# 02_INPUT_PWR_2.net
KiCad netlist of a schematic drawn in Altium Designer
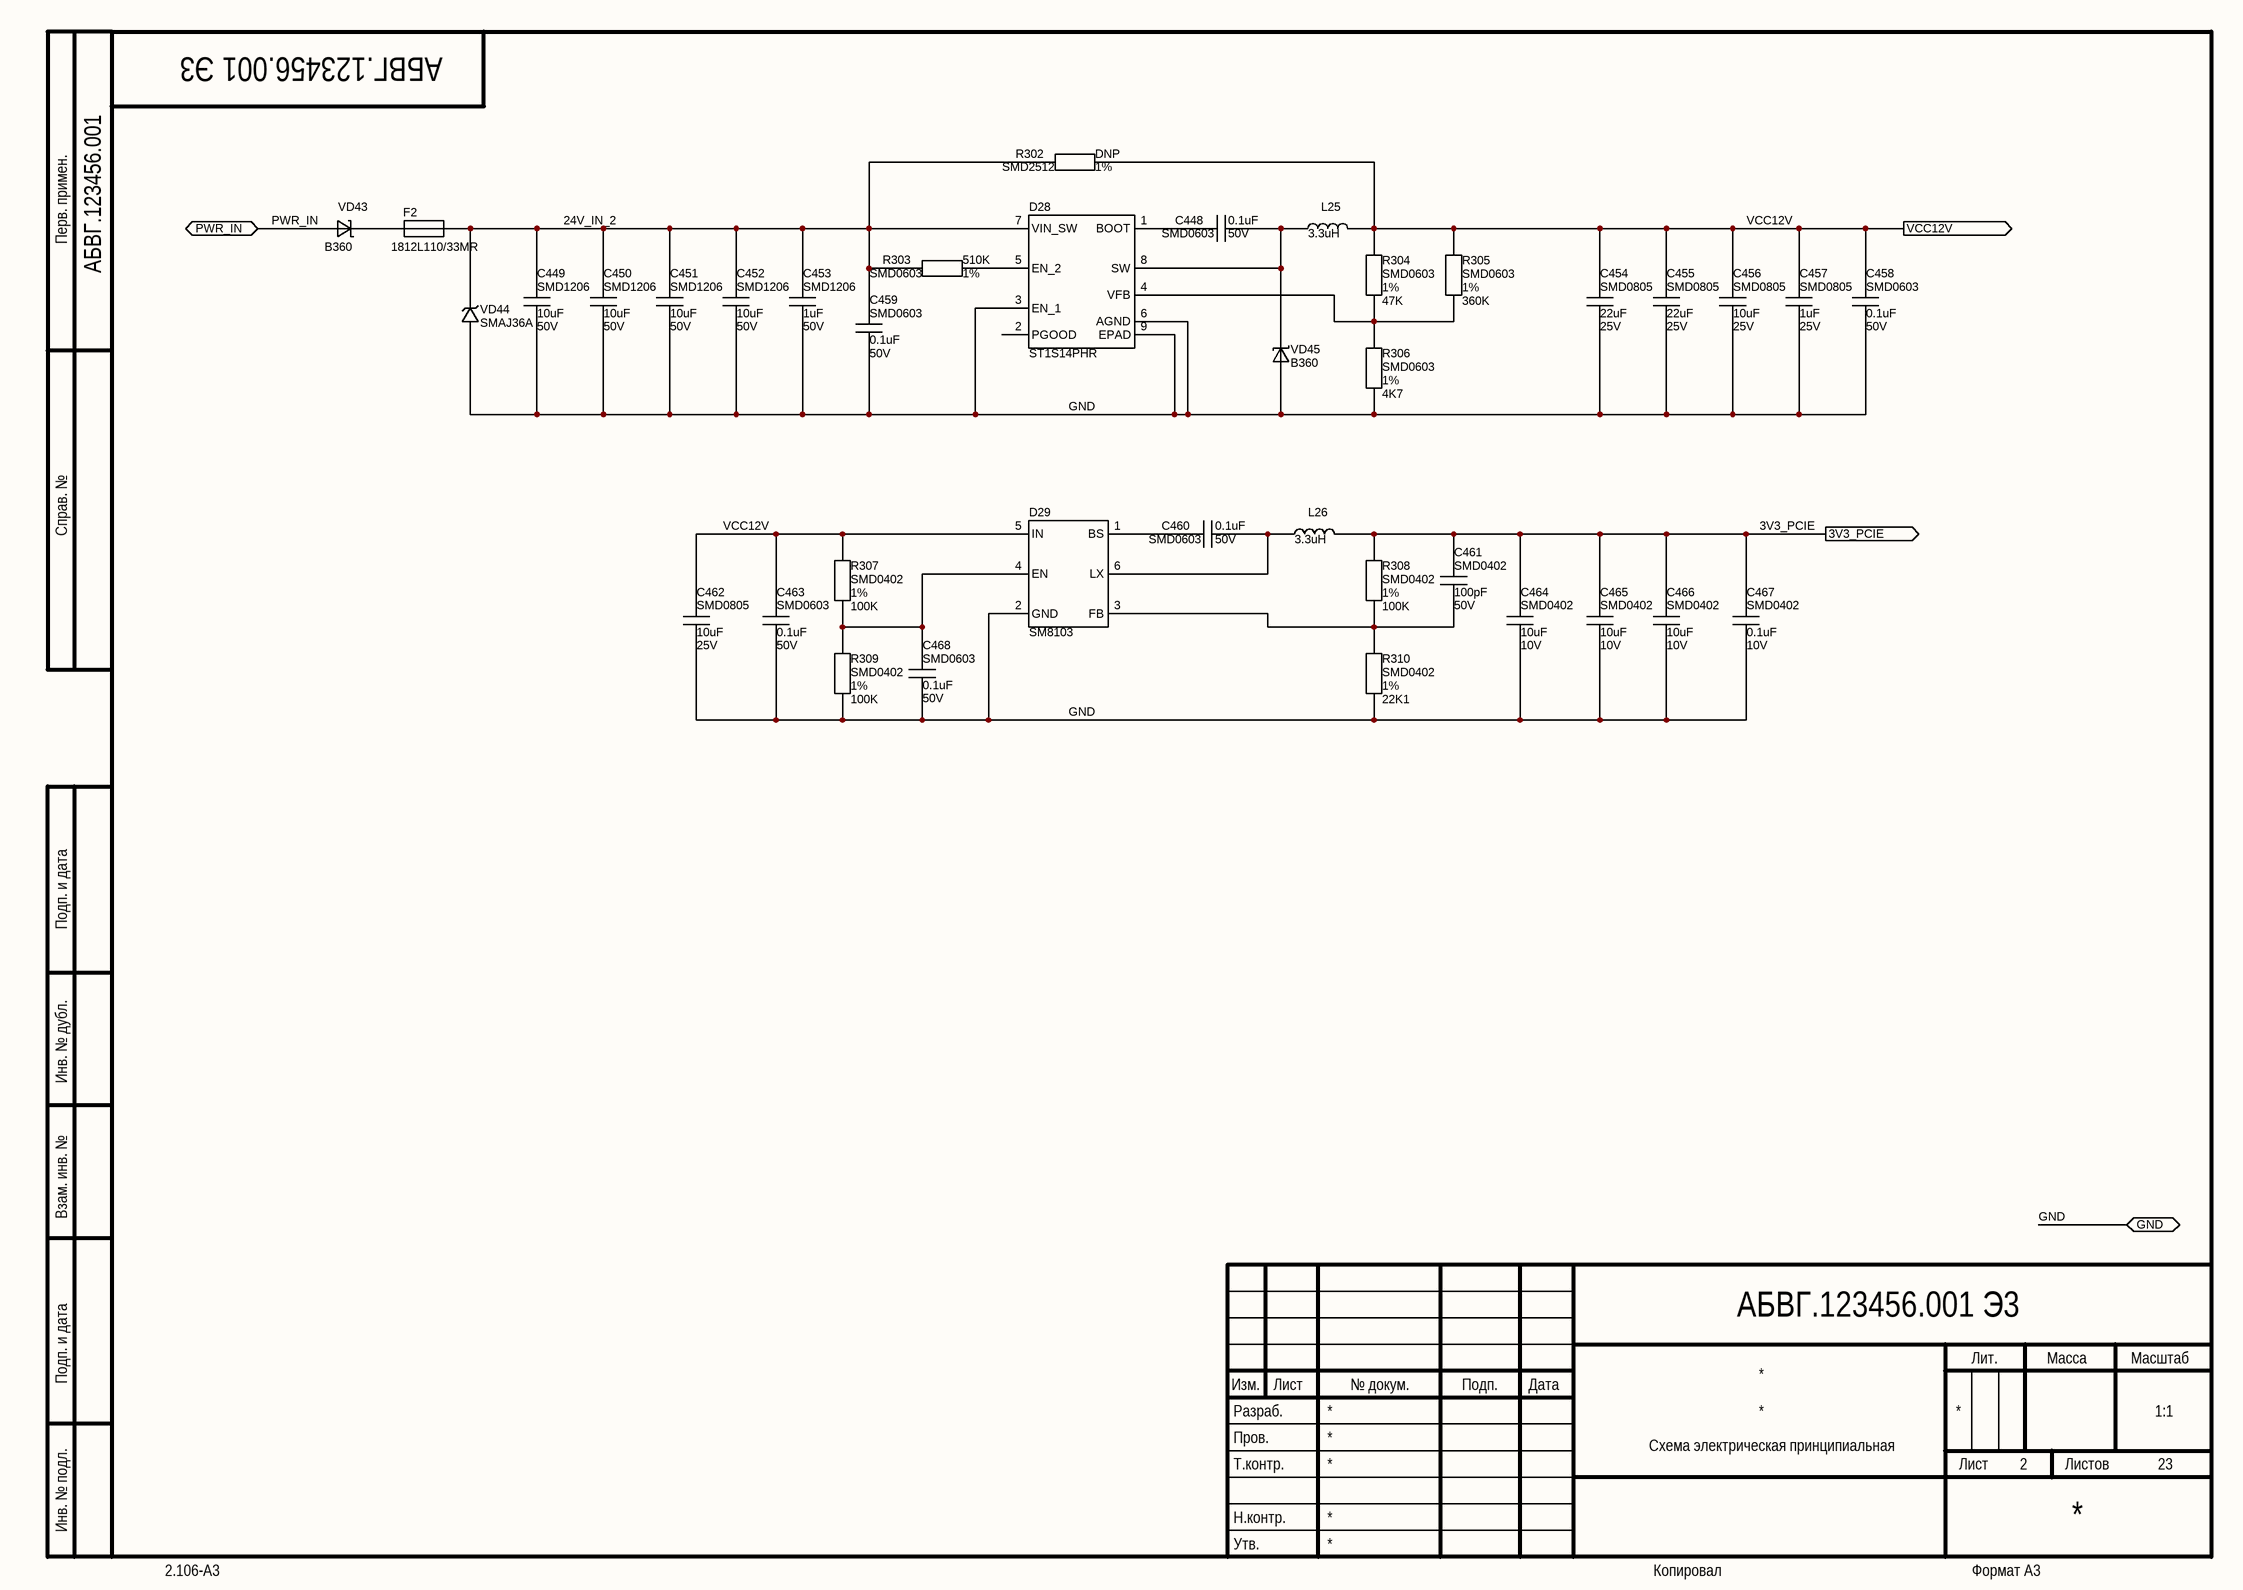
[diagram p0: 02 INPUT_PWR_2.SchDoc]

(export (version "E")
  (design (tool "Eeschema 10.0.6"))
  (components
    (comp (ref "C448")
      (value "0.1uF")
      (footprint "CAP_SMD_0603")
      (fields
        (field (name "PACKAGE") "SMD0603")
        (field (name "PARTNUMBER") "CC0603KRX7R9BB104")
        (field (name "VOLTAGE") "50V")
      )
      (libsource (lib "Didur_SchLib_1") (part "Ceramic_Cap"))
    )
    (comp (ref "C449")
      (value "10uF")
      (footprint "CAP_SMD_1206")
      (fields
        (field (name "PACKAGE") "SMD1206")
        (field (name "PARTNUMBER") "CL31B106KBHNNNE")
        (field (name "VOLTAGE") "50V")
      )
      (libsource (lib "Didur_SchLib_1") (part "Ceramic_Cap"))
    )
    (comp (ref "C450")
      (value "10uF")
      (footprint "CAP_SMD_1206")
      (fields
        (field (name "PACKAGE") "SMD1206")
        (field (name "PARTNUMBER") "CL31B106KBHNNNE")
        (field (name "VOLTAGE") "50V")
      )
      (libsource (lib "Didur_SchLib_1") (part "Ceramic_Cap"))
    )
    (comp (ref "C451")
      (value "10uF")
      (footprint "CAP_SMD_1206")
      (fields
        (field (name "PACKAGE") "SMD1206")
        (field (name "PARTNUMBER") "CL31B106KBHNNNE")
        (field (name "VOLTAGE") "50V")
      )
      (libsource (lib "Didur_SchLib_1") (part "Ceramic_Cap"))
    )
    (comp (ref "C452")
      (value "10uF")
      (footprint "CAP_SMD_1206")
      (fields
        (field (name "PACKAGE") "SMD1206")
        (field (name "PARTNUMBER") "CL31B106KBHNNNE")
        (field (name "VOLTAGE") "50V")
      )
      (libsource (lib "Didur_SchLib_1") (part "Ceramic_Cap"))
    )
    (comp (ref "C453")
      (value "1uF")
      (footprint "CAP_SMD_1206")
      (fields
        (field (name "PACKAGE") "SMD1206")
        (field (name "PARTNUMBER") "CC1206MRY5V9BB105")
        (field (name "VOLTAGE") "50V")
      )
      (libsource (lib "Didur_SchLib_1") (part "Ceramic_Cap"))
    )
    (comp (ref "C454")
      (value "22uF")
      (footprint "CAP_SMD_0805")
      (fields
        (field (name "PACKAGE") "SMD0805")
        (field (name "PARTNUMBER") "CC0805MKX5R8BB226")
        (field (name "VOLTAGE") "25V")
      )
      (libsource (lib "Didur_SchLib_1") (part "Ceramic_Cap"))
    )
    (comp (ref "C455")
      (value "22uF")
      (footprint "CAP_SMD_0805")
      (fields
        (field (name "PACKAGE") "SMD0805")
        (field (name "PARTNUMBER") "CC0805MKX5R8BB226")
        (field (name "VOLTAGE") "25V")
      )
      (libsource (lib "Didur_SchLib_1") (part "Ceramic_Cap"))
    )
    (comp (ref "C456")
      (value "10uF")
      (footprint "CAP_SMD_0805")
      (fields
        (field (name "PACKAGE") "SMD0805")
        (field (name "PARTNUMBER") "CL21A106KAYNNNE")
        (field (name "VOLTAGE") "25V")
      )
      (libsource (lib "Didur_SchLib_1") (part "Ceramic_Cap"))
    )
    (comp (ref "C457")
      (value "1uF")
      (footprint "CAP_SMD_0805")
      (fields
        (field (name "PACKAGE") "SMD0805")
        (field (name "PARTNUMBER") "CC0805KKX7R8BB105")
        (field (name "VOLTAGE") "25V")
      )
      (libsource (lib "Didur_SchLib_1") (part "Ceramic_Cap"))
    )
    (comp (ref "C458")
      (value "0.1uF")
      (footprint "CAP_SMD_0603")
      (fields
        (field (name "PACKAGE") "SMD0603")
        (field (name "PARTNUMBER") "CC0603KRX7R9BB104")
        (field (name "VOLTAGE") "50V")
      )
      (libsource (lib "Didur_SchLib_1") (part "Ceramic_Cap"))
    )
    (comp (ref "C459")
      (value "0.1uF")
      (footprint "CAP_SMD_0603")
      (fields
        (field (name "PACKAGE") "SMD0603")
        (field (name "PARTNUMBER") "CC0603KRX7R9BB104")
        (field (name "VOLTAGE") "50V")
      )
      (libsource (lib "Didur_SchLib_1") (part "Ceramic_Cap"))
    )
    (comp (ref "C460")
      (value "0.1uF")
      (footprint "CAP_SMD_0603")
      (fields
        (field (name "PACKAGE") "SMD0603")
        (field (name "PARTNUMBER") "CC0603KRX7R9BB104")
        (field (name "VOLTAGE") "50V")
      )
      (libsource (lib "Didur_SchLib_1") (part "Ceramic_Cap"))
    )
    (comp (ref "C461")
      (value "100pF")
      (footprint "Didur_PcbLib_1:CAP_SMD_0402")
      (fields
        (field (name "PACKAGE") "SMD0402")
        (field (name "PARTNUMBER") "CC0402KRNPO9BN101")
        (field (name "VOLTAGE") "50V")
      )
      (libsource (lib "Didur_SchLib_1") (part "Ceramic_Cap"))
    )
    (comp (ref "C462")
      (value "10uF")
      (footprint "CAP_SMD_0805")
      (fields
        (field (name "PACKAGE") "SMD0805")
        (field (name "PARTNUMBER") "CL21A106KAYNNNE")
        (field (name "VOLTAGE") "25V")
      )
      (libsource (lib "Didur_SchLib_1") (part "Ceramic_Cap"))
    )
    (comp (ref "C463")
      (value "0.1uF")
      (footprint "CAP_SMD_0603")
      (fields
        (field (name "PACKAGE") "SMD0603")
        (field (name "PARTNUMBER") "CC0603KRX7R9BB104")
        (field (name "VOLTAGE") "50V")
      )
      (libsource (lib "Didur_SchLib_1") (part "Ceramic_Cap"))
    )
    (comp (ref "C464")
      (value "10uF")
      (footprint "Didur_PcbLib_1:CAP_SMD_0402")
      (fields
        (field (name "PACKAGE") "SMD0402")
        (field (name "PARTNUMBER") "CC0402MRX5R6BB106")
        (field (name "VOLTAGE") "10V")
      )
      (libsource (lib "Didur_SchLib_1") (part "Ceramic_Cap"))
    )
    (comp (ref "C465")
      (value "10uF")
      (footprint "Didur_PcbLib_1:CAP_SMD_0402")
      (fields
        (field (name "PACKAGE") "SMD0402")
        (field (name "PARTNUMBER") "CC0402MRX5R6BB106")
        (field (name "VOLTAGE") "10V")
      )
      (libsource (lib "Didur_SchLib_1") (part "Ceramic_Cap"))
    )
    (comp (ref "C466")
      (value "10uF")
      (footprint "Didur_PcbLib_1:CAP_SMD_0402")
      (fields
        (field (name "PACKAGE") "SMD0402")
        (field (name "PARTNUMBER") "CC0402MRX5R6BB106")
        (field (name "VOLTAGE") "10V")
      )
      (libsource (lib "Didur_SchLib_1") (part "Ceramic_Cap"))
    )
    (comp (ref "C467")
      (value "0.1uF")
      (footprint "Didur_PcbLib_1:CAP_SMD_0402")
      (fields
        (field (name "PACKAGE") "SMD0402")
        (field (name "PARTNUMBER") "CC0402KRX5R6BB104")
        (field (name "VOLTAGE") "10V")
      )
      (libsource (lib "Didur_SchLib_1") (part "Ceramic_Cap"))
    )
    (comp (ref "C468")
      (value "0.1uF")
      (footprint "CAP_SMD_0603")
      (fields
        (field (name "PACKAGE") "SMD0603")
        (field (name "PARTNUMBER") "CC0603KRX7R9BB104")
        (field (name "VOLTAGE") "50V")
      )
      (libsource (lib "Didur_SchLib_1") (part "Ceramic_Cap"))
    )
    (comp (ref "D28")
      (value "ST1S14PHR")
      (footprint "SO8_PWR")
      (libsource (lib "Didur_SchLib_1") (part "ST1S14"))
    )
    (comp (ref "D29")
      (value "SM8103")
      (footprint "Didur_PcbLib_1:SOT23-6")
      (libsource (lib "Didur_SchLib_1") (part "SM8103"))
    )
    (comp (ref "F2")
      (value "1812L110/33MR")
      (footprint "Didur_PcbLib_1:FUSE_SMD_1812")
      (fields (field (name "Comment") "Value"))
      (libsource (lib "Didur_SchLib_1") (part "Fuse"))
    )
    (comp (ref "L25")
      (value "3.3uH")
      (footprint "Didur_PcbLib_1:IHLP2020")
      (fields (field (name "PARTNUMBER") "IHLP2020CZER3R3M01") (field (name "Comment") "Value"))
      (libsource (lib "Didur_SchLib_1") (part "Inductor_smal"))
    )
    (comp (ref "L26")
      (value "3.3uH")
      (footprint "Didur_PcbLib_1:IHLP2020")
      (fields (field (name "PARTNUMBER") "IHLP2020CZER3R3M01") (field (name "Comment") "Value"))
      (libsource (lib "Didur_SchLib_1") (part "Inductor_smal"))
    )
    (comp (ref "R302")
      (value "DNP")
      (footprint "RES_SMD_2512")
      (fields
        (field (name "PACKAGE") "SMD2512")
        (field (name "PARTNUMBER") "RC2512FK-070RL")
        (field (name "TOLERANCE") "1%")
      )
      (libsource (lib "Didur_SchLib_1") (part "Chip_Res"))
    )
    (comp (ref "R303")
      (value "510K")
      (footprint "RES_SMD_0603")
      (fields
        (field (name "PACKAGE") "SMD0603")
        (field (name "PARTNUMBER") "RC0603FR-07510KL")
        (field (name "TOLERANCE") "1%")
      )
      (libsource (lib "Didur_SchLib_1") (part "Chip_Res"))
    )
    (comp (ref "R304")
      (value "47K")
      (footprint "RES_SMD_0603")
      (fields
        (field (name "PACKAGE") "SMD0603")
        (field (name "PARTNUMBER") "RC0603FR-0747KL")
        (field (name "TOLERANCE") "1%")
      )
      (libsource (lib "") (part "Chip_Res_1"))
    )
    (comp (ref "R305")
      (value "360K")
      (footprint "RES_SMD_0603")
      (fields
        (field (name "PACKAGE") "SMD0603")
        (field (name "PARTNUMBER") "RC0603FR-07360KL")
        (field (name "TOLERANCE") "1%")
      )
      (libsource (lib "") (part "Chip_Res_1"))
    )
    (comp (ref "R306")
      (value "4K7")
      (footprint "RES_SMD_0603")
      (fields
        (field (name "PACKAGE") "SMD0603")
        (field (name "PARTNUMBER") "RC0603FR-074K7L")
        (field (name "TOLERANCE") "1%")
      )
      (libsource (lib "") (part "Chip_Res_1"))
    )
    (comp (ref "R307")
      (value "100K")
      (footprint "Didur_PcbLib_1:RES_SMD_0402")
      (fields
        (field (name "PACKAGE") "SMD0402")
        (field (name "PARTNUMBER") "RC0402FR-07100KL")
        (field (name "TOLERANCE") "1%")
      )
      (libsource (lib "") (part "Chip_Res_1"))
    )
    (comp (ref "R308")
      (value "100K")
      (footprint "Didur_PcbLib_1:RES_SMD_0402")
      (fields
        (field (name "PACKAGE") "SMD0402")
        (field (name "PARTNUMBER") "RC0402FR-07100KL")
        (field (name "TOLERANCE") "1%")
      )
      (libsource (lib "") (part "Chip_Res_1"))
    )
    (comp (ref "R309")
      (value "100K")
      (footprint "Didur_PcbLib_1:RES_SMD_0402")
      (fields
        (field (name "PACKAGE") "SMD0402")
        (field (name "PARTNUMBER") "RC0402FR-07100KL")
        (field (name "TOLERANCE") "1%")
      )
      (libsource (lib "") (part "Chip_Res_1"))
    )
    (comp (ref "R310")
      (value "22K1")
      (footprint "Didur_PcbLib_1:RES_SMD_0402")
      (fields
        (field (name "PACKAGE") "SMD0402")
        (field (name "PARTNUMBER") "RC0402FR-0722K1L")
        (field (name "TOLERANCE") "1%")
      )
      (libsource (lib "") (part "Chip_Res_1"))
    )
    (comp (ref "VD43")
      (value "B360")
      (footprint "Didur_PcbLib_1:SMA")
      (fields (field (name "Comment") "Value"))
      (libsource (lib "Didur_SchLib_1") (part "ShottkyDiode"))
    )
    (comp (ref "VD44")
      (value "SMAJ36A")
      (footprint "Didur_PcbLib_1:SMA")
      (libsource (lib "Didur_SchLib_1") (part "ZenerDiode"))
    )
    (comp (ref "VD45")
      (value "B360")
      (footprint "Didur_PcbLib_1:SMA")
      (fields (field (name "Comment") "Value"))
      (libsource (lib "Didur_SchLib_1") (part "ShottkyDiode"))
    )
  )
  (nets
    (net (code "1") (name "/3V3_PCIE") (class "Default")
      (node (ref "C461") (pin "1") (pinfunction "1_1") (pintype "power_in"))
      (node (ref "C464") (pin "1") (pinfunction "1_1") (pintype "power_in"))
      (node (ref "C465") (pin "1") (pinfunction "1_1") (pintype "power_in"))
      (node (ref "C466") (pin "1") (pinfunction "1_1") (pintype "power_in"))
      (node (ref "C467") (pin "1") (pinfunction "1_1") (pintype "power_in"))
      (node (ref "L26") (pin "1") (pinfunction "1_1") (pintype "passive"))
      (node (ref "R308") (pin "2") (pinfunction "2_2") (pintype "passive"))
    )
    (net (code "2") (name "/24V_IN_2") (class "Default")
      (node (ref "C449") (pin "2") (pinfunction "2_2") (pintype "power_in"))
      (node (ref "C450") (pin "2") (pinfunction "2_2") (pintype "power_in"))
      (node (ref "C451") (pin "2") (pinfunction "2_2") (pintype "power_in"))
      (node (ref "C452") (pin "2") (pinfunction "2_2") (pintype "power_in"))
      (node (ref "C453") (pin "2") (pinfunction "2_2") (pintype "power_in"))
      (node (ref "C459") (pin "2") (pinfunction "2_2") (pintype "power_in"))
      (node (ref "D28") (pin "7") (pinfunction "VIN_SW_7") (pintype "passive"))
      (node (ref "F2") (pin "2") (pinfunction "2_2") (pintype "passive"))
      (node (ref "R302") (pin "1") (pinfunction "1_1") (pintype "passive"))
      (node (ref "R303") (pin "1") (pinfunction "1_1") (pintype "passive"))
      (node (ref "VD44") (pin "2") (pinfunction "C_2") (pintype "passive"))
    )
    (net (code "3") (name "/GND") (class "Default")
      (node (ref "C449") (pin "1") (pinfunction "1_1") (pintype "power_in"))
      (node (ref "C450") (pin "1") (pinfunction "1_1") (pintype "power_in"))
      (node (ref "C451") (pin "1") (pinfunction "1_1") (pintype "power_in"))
      (node (ref "C452") (pin "1") (pinfunction "1_1") (pintype "power_in"))
      (node (ref "C453") (pin "1") (pinfunction "1_1") (pintype "power_in"))
      (node (ref "C454") (pin "1") (pinfunction "1_1") (pintype "power_in"))
      (node (ref "C455") (pin "1") (pinfunction "1_1") (pintype "power_in"))
      (node (ref "C456") (pin "1") (pinfunction "1_1") (pintype "power_in"))
      (node (ref "C457") (pin "1") (pinfunction "1_1") (pintype "power_in"))
      (node (ref "C458") (pin "1") (pinfunction "1_1") (pintype "power_in"))
      (node (ref "C459") (pin "1") (pinfunction "1_1") (pintype "power_in"))
      (node (ref "C462") (pin "1") (pinfunction "1_1") (pintype "power_in"))
      (node (ref "C463") (pin "1") (pinfunction "1_1") (pintype "power_in"))
      (node (ref "C464") (pin "2") (pinfunction "2_2") (pintype "power_in"))
      (node (ref "C465") (pin "2") (pinfunction "2_2") (pintype "power_in"))
      (node (ref "C466") (pin "2") (pinfunction "2_2") (pintype "power_in"))
      (node (ref "C467") (pin "2") (pinfunction "2_2") (pintype "power_in"))
      (node (ref "C468") (pin "1") (pinfunction "1_1") (pintype "power_in"))
      (node (ref "D28") (pin "3") (pinfunction "EN_1_3") (pintype "passive"))
      (node (ref "D28") (pin "6") (pinfunction "AGND_6") (pintype "passive"))
      (node (ref "D28") (pin "9") (pinfunction "EPAD_9") (pintype "passive"))
      (node (ref "D29") (pin "2") (pinfunction "GND_2") (pintype "passive"))
      (node (ref "R306") (pin "1") (pinfunction "1_1") (pintype "passive"))
      (node (ref "R309") (pin "1") (pinfunction "1_1") (pintype "passive"))
      (node (ref "R310") (pin "1") (pinfunction "1_1") (pintype "passive"))
      (node (ref "VD44") (pin "1") (pinfunction "A_1") (pintype "passive"))
      (node (ref "VD45") (pin "1") (pinfunction "A_1") (pintype "passive"))
    )
    (net (code "4") (name "/PWR_IN") (class "Default")
      (node (ref "VD43") (pin "1") (pinfunction "A_1") (pintype "passive"))
    )
    (net (code "5") (name "/VCC12V") (class "Default")
      (node (ref "C454") (pin "2") (pinfunction "2_2") (pintype "power_in"))
      (node (ref "C455") (pin "2") (pinfunction "2_2") (pintype "power_in"))
      (node (ref "C456") (pin "2") (pinfunction "2_2") (pintype "power_in"))
      (node (ref "C457") (pin "2") (pinfunction "2_2") (pintype "power_in"))
      (node (ref "C458") (pin "2") (pinfunction "2_2") (pintype "power_in"))
      (node (ref "C462") (pin "2") (pinfunction "2_2") (pintype "power_in"))
      (node (ref "C463") (pin "2") (pinfunction "2_2") (pintype "power_in"))
      (node (ref "D29") (pin "5") (pinfunction "IN_5") (pintype "passive"))
      (node (ref "L25") (pin "1") (pinfunction "1_1") (pintype "passive"))
      (node (ref "R302") (pin "2") (pinfunction "2_2") (pintype "passive"))
      (node (ref "R304") (pin "2") (pinfunction "2_2") (pintype "passive"))
      (node (ref "R305") (pin "2") (pinfunction "2_2") (pintype "passive"))
      (node (ref "R307") (pin "2") (pinfunction "2_2") (pintype "passive"))
    )
    (net (code "6") (name "Net-(D28-BOOT)") (class "Default")
      (node (ref "C448") (pin "2") (pinfunction "2_2") (pintype "power_in"))
      (node (ref "D28") (pin "1") (pinfunction "BOOT_1") (pintype "passive"))
    )
    (net (code "7") (name "Net-(D28-EN_2)") (class "Default")
      (node (ref "D28") (pin "5") (pinfunction "EN_2_5") (pintype "passive"))
      (node (ref "R303") (pin "2") (pinfunction "2_2") (pintype "passive"))
    )
    (net (code "8") (name "Net-(D28-SW)") (class "Default")
      (node (ref "C448") (pin "1") (pinfunction "1_1") (pintype "power_in"))
      (node (ref "D28") (pin "8") (pinfunction "SW_8") (pintype "passive"))
      (node (ref "L25") (pin "2") (pinfunction "2_2") (pintype "passive"))
      (node (ref "VD45") (pin "2") (pinfunction "C_2") (pintype "passive"))
    )
    (net (code "9") (name "Net-(D28-VFB)") (class "Default")
      (node (ref "D28") (pin "4") (pinfunction "VFB_4") (pintype "passive"))
      (node (ref "R304") (pin "1") (pinfunction "1_1") (pintype "passive"))
      (node (ref "R305") (pin "1") (pinfunction "1_1") (pintype "passive"))
      (node (ref "R306") (pin "2") (pinfunction "2_2") (pintype "passive"))
    )
    (net (code "10") (name "Net-(D29-BS)") (class "Default")
      (node (ref "C460") (pin "2") (pinfunction "2_2") (pintype "power_in"))
      (node (ref "D29") (pin "1") (pinfunction "BS_1") (pintype "passive"))
    )
    (net (code "11") (name "Net-(D29-EN)") (class "Default")
      (node (ref "C468") (pin "2") (pinfunction "2_2") (pintype "power_in"))
      (node (ref "D29") (pin "4") (pinfunction "EN_4") (pintype "passive"))
      (node (ref "R307") (pin "1") (pinfunction "1_1") (pintype "passive"))
      (node (ref "R309") (pin "2") (pinfunction "2_2") (pintype "passive"))
    )
    (net (code "12") (name "Net-(D29-FB)") (class "Default")
      (node (ref "C461") (pin "2") (pinfunction "2_2") (pintype "power_in"))
      (node (ref "D29") (pin "3") (pinfunction "FB_3") (pintype "passive"))
      (node (ref "R308") (pin "1") (pinfunction "1_1") (pintype "passive"))
      (node (ref "R310") (pin "2") (pinfunction "2_2") (pintype "passive"))
    )
    (net (code "13") (name "Net-(D29-LX)") (class "Default")
      (node (ref "C460") (pin "1") (pinfunction "1_1") (pintype "power_in"))
      (node (ref "D29") (pin "6") (pinfunction "LX_6") (pintype "passive"))
      (node (ref "L26") (pin "2") (pinfunction "2_2") (pintype "passive"))
    )
    (net (code "14") (name "Net-(VD43-C)") (class "Default")
      (node (ref "F2") (pin "1") (pinfunction "1_1") (pintype "passive"))
      (node (ref "VD43") (pin "2") (pinfunction "C_2") (pintype "passive"))
    )
    (net (code "15") (name "unconnected-(D28-PGOOD-Pad2)") (class "Default")
      (node (ref "D28") (pin "2") (pinfunction "PGOOD_2") (pintype "passive"))
    )
  )
)
